# DCDC.net
KiCad netlist of a schematic drawn in Altium Designer
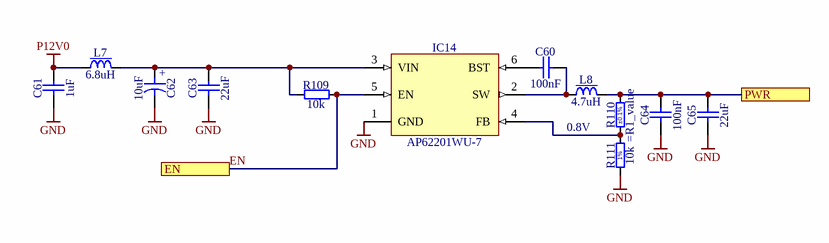
[diagram p0: DCDC.SchDoc]

(export (version "E")
  (design (tool "Eeschema 10.0.6"))
  (components
    (comp (ref "C60")
      (value "100nF")
      (footprint "CAPC1005X55N")
      (description "Non-polarised capacitor")
      (fields
        (field (name "PART NUMBER") "CC0402_100NF_16V_10%_X5R")
        (field (name "VOLTAGE") "16V")
        (field (name "AUTHOR") "CERN DEM JLC")
      )
      (libsource (lib "Capacitors") (part "Capacitor - non polarized"))
    )
    (comp (ref "C61")
      (value "1uF")
      (footprint "CAPC1608X87N")
      (description "Non-polarised capacitor")
      (fields
        (field (name "PART NUMBER") "CC0603_1UF_25V_10%_X7R")
        (field (name "VOLTAGE") "25V")
        (field (name "AUTHOR") "CERN DEM JLC")
      )
      (libsource (lib "Capacitors") (part "Capacitor - non polarized"))
    )
    (comp (ref "C62")
      (value "10uF")
      (footprint "CAPMP3216X180N")
      (description "Polarised capacitor")
      (fields
        (field (name "PART NUMBER") "CTE3216-18_10UF_16V_20%_AVX_TCJ")
        (field (name "VOLTAGE") "16V")
        (field (name "AUTHOR") "CERN DEM JLC")
      )
      (libsource (lib "Capacitors") (part "Capacitor - polarized"))
    )
    (comp (ref "C63")
      (value "22uF")
      (footprint "CAPC2012X135N")
      (description "Non-polarised capacitor")
      (fields
        (field (name "PART NUMBER") "CC0805_22UF_16V_10%_X5R")
        (field (name "VOLTAGE") "16V")
        (field (name "AUTHOR") "CERN DEM JLC")
      )
      (libsource (lib "Capacitors") (part "Capacitor - non polarized"))
    )
    (comp (ref "C64")
      (value "100nF")
      (footprint "CAPC1005X55N")
      (description "Non-polarised capacitor")
      (fields
        (field (name "PART NUMBER") "CC0402_100NF_16V_10%_X5R")
        (field (name "VOLTAGE") "16V")
        (field (name "AUTHOR") "CERN DEM JLC")
      )
      (libsource (lib "Capacitors") (part "Capacitor - non polarized"))
    )
    (comp (ref "C65")
      (value "22uF")
      (footprint "CAPC2012X135N")
      (description "Non-polarised capacitor")
      (fields
        (field (name "PART NUMBER") "CC0805_22UF_16V_10%_X5R")
        (field (name "VOLTAGE") "16V")
        (field (name "AUTHOR") "CERN DEM JLC")
      )
      (libsource (lib "Capacitors") (part "Capacitor - non polarized"))
    )
    (comp (ref "IC14")
      (value "AP62201WU-7")
      (footprint "SOT95P280X100-6N")
      (description "4.2V TO 18V INPUT, 2A LOW IQ SYNCHRONOUS BUCK CONVERTER")
      (fields (field (name "MANUFACTURER") "DIODES INCORPORATED") (field (name "AUTHOR") "CERN DEM HF"))
      (libsource (lib "Magneto") (part "AP62201WU-7"))
    )
    (comp (ref "L7")
      (value "6.8uH")
      (footprint "IND_COILCRAFT_XAL4030")
      (description "Inductor With Core")
      (fields
        (field (name "PART NUMBER") "IND_6.8UH_20%_COILCRAFT_XAL4030")
        (field (name "POWER") "3A")
        (field (name "AUTHOR") "CERN DEM MR")
      )
      (libsource (lib "Inductors & Transformers") (part "Inductor With Magnetic core"))
    )
    (comp (ref "L8")
      (value "4.7uH")
      (footprint "IND_WURTH_WE-SPC-4838")
      (description "Inductor With Core")
      (fields
        (field (name "PART NUMBER") "IND_4.7UH_20%_WURTH_WE-SPC_74408943047")
        (field (name "POWER") "2.2A")
        (field (name "AUTHOR") "CERN DEM JLC")
      )
      (libsource (lib "Inductors & Transformers") (part "Inductor With Magnetic core"))
    )
    (comp (ref "R109")
      (value "10k")
      (footprint "RESC1608X55N")
      (description "Resistor - 1%")
      (fields
        (field (name "PART NUMBER") "R0603_10K_1%_0.1W_100PPM")
        (field (name "POWER") "0.1W")
        (field (name "AUTHOR") "CERN DEM JLC")
      )
      (libsource (lib "") (part "Resistor - 1%_1"))
    )
    (comp (ref "R110")
      (value "~")
      (footprint "RESC1608X55N")
      (description "Resistor - 0.1%")
      (fields
        (field (name "TOLERANCE") "±0.1%")
        (field (name "PART NUMBER") "R0603_52R3_0.1%_0.063W_10PPM")
        (field (name "POWER") "0.063W")
        (field (name "AUTHOR") "CERN DEM JLC")
      )
      (libsource (lib "Resistors") (part "Resistor - 0.1%"))
    )
    (comp (ref "R111")
      (value "10k")
      (footprint "RESC1005X40N")
      (description "Resistor - 1%")
      (fields
        (field (name "PART NUMBER") "R0402_10K_1%_0.0625W_100PPM")
        (field (name "POWER") "0.0625W")
        (field (name "AUTHOR") "CERN DEM JLC")
      )
      (libsource (lib "Resistors") (part "Resistor - 1%"))
    )
  )
  (nets
    (net (code "1") (name "/EN") (class "Default")
      (node (ref "IC14") (pin "5") (pinfunction "EN_5") (pintype "input"))
      (node (ref "R109") (pin "2") (pinfunction "2_2") (pintype "passive"))
    )
    (net (code "2") (name "/PWR") (class "Default")
      (node (ref "C64") (pin "2") (pinfunction "2_2") (pintype "passive"))
      (node (ref "C65") (pin "2") (pinfunction "2_2") (pintype "passive"))
      (node (ref "L8") (pin "2") (pinfunction "2_2") (pintype "passive"))
      (node (ref "R110") (pin "2") (pinfunction "2_2") (pintype "passive"))
    )
    (net (code "3") (name "GND") (class "Default")
      (node (ref "C61") (pin "1") (pinfunction "1_1") (pintype "passive"))
      (node (ref "C62") (pin "2") (pinfunction "2_2") (pintype "passive"))
      (node (ref "C63") (pin "1") (pinfunction "1_1") (pintype "passive"))
      (node (ref "C64") (pin "1") (pinfunction "1_1") (pintype "passive"))
      (node (ref "C65") (pin "1") (pinfunction "1_1") (pintype "passive"))
      (node (ref "IC14") (pin "1") (pinfunction "GND_1") (pintype "power_in"))
      (node (ref "R111") (pin "1") (pinfunction "1_1") (pintype "passive"))
    )
    (net (code "4") (name "Net-(IC14-BST)") (class "Default")
      (node (ref "C60") (pin "1") (pinfunction "1_1") (pintype "passive"))
      (node (ref "IC14") (pin "6") (pinfunction "BST_6") (pintype "input"))
    )
    (net (code "5") (name "Net-(IC14-FB)") (class "Default")
      (node (ref "IC14") (pin "4") (pinfunction "FB_4") (pintype "input"))
      (node (ref "R110") (pin "1") (pinfunction "1_1") (pintype "passive"))
      (node (ref "R111") (pin "2") (pinfunction "2_2") (pintype "passive"))
    )
    (net (code "6") (name "Net-(IC14-SW)") (class "Default")
      (node (ref "C60") (pin "2") (pinfunction "2_2") (pintype "passive"))
      (node (ref "IC14") (pin "2") (pinfunction "SW_2") (pintype "output"))
      (node (ref "L8") (pin "1") (pinfunction "1_1") (pintype "passive"))
    )
    (net (code "7") (name "Net-(IC14-VIN)") (class "Default")
      (node (ref "C62") (pin "1") (pinfunction "1_1") (pintype "passive"))
      (node (ref "C63") (pin "2") (pinfunction "2_2") (pintype "passive"))
      (node (ref "IC14") (pin "3") (pinfunction "VIN_3") (pintype "input"))
      (node (ref "L7") (pin "2") (pinfunction "2_2") (pintype "passive"))
      (node (ref "R109") (pin "1") (pinfunction "1_1") (pintype "passive"))
    )
    (net (code "8") (name "P12V0") (class "Default")
      (node (ref "C61") (pin "2") (pinfunction "2_2") (pintype "passive"))
      (node (ref "L7") (pin "1") (pinfunction "1_1") (pintype "passive"))
    )
  )
)
